# circuit.net
KiCad netlist of a schematic drawn in Altium Designer
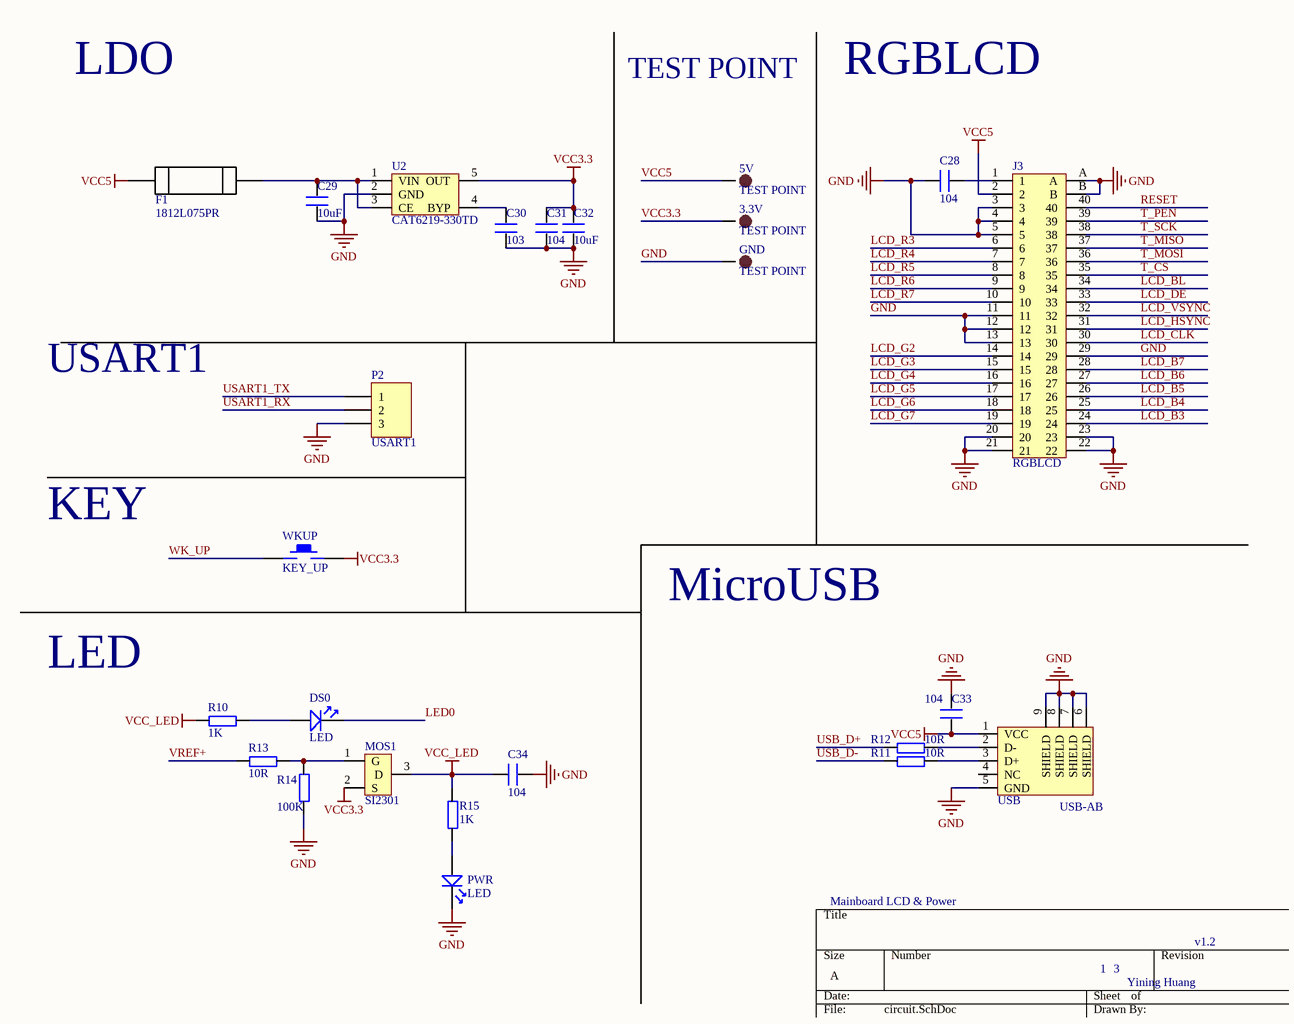
[diagram p0: circuit.SchDoc]

(export (version "E")
  (design (tool "Eeschema 10.0.6"))
  (components
    (comp (ref "3.3V")
      (value "TEST POINT")
      (footprint "TP-1.5")
      (description "测试点")
      (libsource (lib "STM32F767核心板封装库") (part "TEST-POINT"))
    )
    (comp (ref "5V")
      (value "TEST POINT")
      (footprint "TP-1.5")
      (description "测试点")
      (libsource (lib "STM32F767核心板封装库") (part "TEST-POINT"))
    )
    (comp (ref "C28") (value "104") (footprint "0805") (libsource (lib "STM32F767核心板封装库") (part "C")))
    (comp (ref "C29") (value "10uF") (footprint "0805") (libsource (lib "STM32F767核心板封装库") (part "C")))
    (comp (ref "C30") (value "103") (footprint "0805") (libsource (lib "STM32F767核心板封装库") (part "C")))
    (comp (ref "C31") (value "104") (footprint "0805") (libsource (lib "STM32F767核心板封装库") (part "C")))
    (comp (ref "C32") (value "10uF") (footprint "0805") (libsource (lib "STM32F767核心板封装库") (part "C")))
    (comp (ref "C33") (value "104") (footprint "0805") (libsource (lib "STM32F767核心板封装库") (part "C")))
    (comp (ref "C34") (value "104") (footprint "0805") (libsource (lib "STM32F767核心板封装库") (part "C")))
    (comp (ref "DS0")
      (value "LED")
      (footprint "SMDLED-0603")
      (libsource (lib "STM32F767核心板封装库") (part "LED"))
    )
    (comp (ref "F1")
      (value "1812L075PR")
      (footprint "*1812")
      (description "PTC Resettable Fuse 0.75A_hold_ 1.5A_trip_ 13.2VDC 100A 0.8W 0.2s 0.1Ohm SMD Solder Pad 1812 T/R")
      (fields (field (name "MF") "Littelfuse Inc."))
      (libsource (lib "1812L075PR") (part "1812L075PR"))
    )
    (comp (ref "GND")
      (value "TEST POINT")
      (footprint "TP-1.5")
      (description "测试点")
      (libsource (lib "STM32F767核心板封装库") (part "TEST-POINT"))
    )
    (comp (ref "J3")
      (value "RGBLCD")
      (footprint "FPC-TOP40")
      (description "FPC-40P-0.5mm")
      (libsource (lib "STM32F767核心板封装库") (part "FPC-40"))
    )
    (comp (ref "MOS1")
      (value "SI2301")
      (footprint "SO-G3/C2.5")
      (description "IRLML6401/SI2301")
      (libsource (lib "STM32F767核心板封装库") (part "MOS-P"))
    )
    (comp (ref "P2")
      (value "USART1")
      (footprint "HDR1X3")
      (description "Header, 3-Pin")
      (fields (field (name "PUBLISHER") "Altium Limited"))
      (libsource (lib "STM32F767核心板封装库") (part "Header 3"))
    )
    (comp (ref "PWR")
      (value "LED")
      (footprint "SMDLED-0603")
      (libsource (lib "STM32F767核心板封装库") (part "LED"))
    )
    (comp (ref "R10") (value "1K") (footprint "0805") (libsource (lib "STM32F767核心板封装库") (part "R")))
    (comp (ref "R11") (value "10R") (footprint "0805") (libsource (lib "STM32F767核心板封装库") (part "R")))
    (comp (ref "R12") (value "10R") (footprint "0805") (libsource (lib "STM32F767核心板封装库") (part "R")))
    (comp (ref "R13") (value "10R") (footprint "0805") (libsource (lib "STM32F767核心板封装库") (part "R")))
    (comp (ref "R14") (value "100K") (footprint "0805") (libsource (lib "STM32F767核心板封装库") (part "R")))
    (comp (ref "R15") (value "1K") (footprint "0805") (libsource (lib "STM32F767核心板封装库") (part "R")))
    (comp (ref "U2")
      (value "CAT6219-330TD")
      (footprint "SOT-23-5")
      (description "3.3V 500mA LDO")
      (libsource (lib "STM32F767核心板封装库") (part "CAT6219-330TD"))
    )
    (comp (ref "USB")
      (value "USB-AB")
      (footprint "USB_AB - 5S - B")
      (description "MicroUSB")
      (libsource (lib "STM32F767核心板封装库") (part "USB-AB"))
    )
    (comp (ref "WKUP")
      (value "KEY_UP")
      (footprint "KEY_SOP3625")
      (libsource (lib "STM32F767核心板封装库") (part "KEY_M"))
    )
  )
  (nets
    (net (code "1") (name "/LCD_B3") (class "Default")
      (node (ref "J3") (pin "24") (pinfunction "24_24") (pintype "passive"))
    )
    (net (code "2") (name "/LCD_B4") (class "Default")
      (node (ref "J3") (pin "25") (pinfunction "25_25") (pintype "passive"))
    )
    (net (code "3") (name "/LCD_B5") (class "Default")
      (node (ref "J3") (pin "26") (pinfunction "26_26") (pintype "passive"))
    )
    (net (code "4") (name "/LCD_B6") (class "Default")
      (node (ref "J3") (pin "27") (pinfunction "27_27") (pintype "passive"))
    )
    (net (code "5") (name "/LCD_B7") (class "Default")
      (node (ref "J3") (pin "28") (pinfunction "28_28") (pintype "passive"))
    )
    (net (code "6") (name "/LCD_BL") (class "Default")
      (node (ref "J3") (pin "34") (pinfunction "34_34") (pintype "passive"))
    )
    (net (code "7") (name "/LCD_CLK") (class "Default")
      (node (ref "J3") (pin "30") (pinfunction "30_30") (pintype "passive"))
    )
    (net (code "8") (name "/LCD_DE") (class "Default")
      (node (ref "J3") (pin "33") (pinfunction "33_33") (pintype "passive"))
    )
    (net (code "9") (name "/LCD_G2") (class "Default")
      (node (ref "J3") (pin "14") (pinfunction "14_14") (pintype "passive"))
    )
    (net (code "10") (name "/LCD_G3") (class "Default")
      (node (ref "J3") (pin "15") (pinfunction "15_15") (pintype "passive"))
    )
    (net (code "11") (name "/LCD_G4") (class "Default")
      (node (ref "J3") (pin "16") (pinfunction "16_16") (pintype "passive"))
    )
    (net (code "12") (name "/LCD_G5") (class "Default")
      (node (ref "J3") (pin "17") (pinfunction "17_17") (pintype "passive"))
    )
    (net (code "13") (name "/LCD_G6") (class "Default")
      (node (ref "J3") (pin "18") (pinfunction "18_18") (pintype "passive"))
    )
    (net (code "14") (name "/LCD_G7") (class "Default")
      (node (ref "J3") (pin "19") (pinfunction "19_19") (pintype "passive"))
    )
    (net (code "15") (name "/LCD_HSYNC") (class "Default")
      (node (ref "J3") (pin "31") (pinfunction "31_31") (pintype "passive"))
    )
    (net (code "16") (name "/LCD_R3") (class "Default")
      (node (ref "J3") (pin "6") (pinfunction "6_6") (pintype "passive"))
    )
    (net (code "17") (name "/LCD_R4") (class "Default")
      (node (ref "J3") (pin "7") (pinfunction "7_7") (pintype "passive"))
    )
    (net (code "18") (name "/LCD_R5") (class "Default")
      (node (ref "J3") (pin "8") (pinfunction "8_8") (pintype "passive"))
    )
    (net (code "19") (name "/LCD_R6") (class "Default")
      (node (ref "J3") (pin "9") (pinfunction "9_9") (pintype "passive"))
    )
    (net (code "20") (name "/LCD_R7") (class "Default")
      (node (ref "J3") (pin "10") (pinfunction "10_10") (pintype "passive"))
    )
    (net (code "21") (name "/LCD_VSYNC") (class "Default")
      (node (ref "J3") (pin "32") (pinfunction "32_32") (pintype "passive"))
    )
    (net (code "22") (name "/LED0") (class "Default")
      (node (ref "DS0") (pin "2") (pinfunction "2_2") (pintype "passive"))
    )
    (net (code "23") (name "/RESET") (class "Default")
      (node (ref "J3") (pin "40") (pinfunction "40_40") (pintype "passive"))
    )
    (net (code "24") (name "/T_CS") (class "Default")
      (node (ref "J3") (pin "35") (pinfunction "35_35") (pintype "passive"))
    )
    (net (code "25") (name "/T_MISO") (class "Default")
      (node (ref "J3") (pin "37") (pinfunction "37_37") (pintype "passive"))
    )
    (net (code "26") (name "/T_MOSI") (class "Default")
      (node (ref "J3") (pin "36") (pinfunction "36_36") (pintype "passive"))
    )
    (net (code "27") (name "/T_PEN") (class "Default")
      (node (ref "J3") (pin "39") (pinfunction "39_39") (pintype "passive"))
    )
    (net (code "28") (name "/T_SCK") (class "Default")
      (node (ref "J3") (pin "38") (pinfunction "38_38") (pintype "passive"))
    )
    (net (code "29") (name "/USART1_RX") (class "Default")
      (node (ref "P2") (pin "2") (pinfunction "2_2") (pintype "passive"))
    )
    (net (code "30") (name "/USART1_TX") (class "Default")
      (node (ref "P2") (pin "1") (pinfunction "1_1") (pintype "passive"))
    )
    (net (code "31") (name "/USB_D+") (class "Default") (node (ref "R12") (pin "1") (pintype "passive")))
    (net (code "32") (name "/USB_D-") (class "Default") (node (ref "R11") (pin "1") (pintype "passive")))
    (net (code "33") (name "/VREF+") (class "Default") (node (ref "R13") (pin "1") (pintype "passive")))
    (net (code "34") (name "/WK_UP") (class "Default")
      (node (ref "WKUP") (pin "1") (pinfunction "1_1") (pintype "passive"))
    )
    (net (code "35") (name "GND") (class "Default")
      (node (ref "C28") (pin "1") (pintype "passive"))
      (node (ref "C29") (pin "1") (pintype "passive"))
      (node (ref "C30") (pin "1") (pintype "passive"))
      (node (ref "C31") (pin "1") (pintype "passive"))
      (node (ref "C32") (pin "1") (pintype "passive"))
      (node (ref "C33") (pin "2") (pintype "passive"))
      (node (ref "C34") (pin "2") (pintype "passive"))
      (node (ref "GND") (pin "1") (pinfunction "1_1") (pintype "passive"))
      (node (ref "J3") (pin "11") (pinfunction "11_11") (pintype "passive"))
      (node (ref "J3") (pin "12") (pinfunction "12_12") (pintype "passive"))
      (node (ref "J3") (pin "13") (pinfunction "13_13") (pintype "passive"))
      (node (ref "J3") (pin "20") (pinfunction "20_20") (pintype "passive"))
      (node (ref "J3") (pin "21") (pinfunction "21_21") (pintype "passive"))
      (node (ref "J3") (pin "22") (pinfunction "22_22") (pintype "passive"))
      (node (ref "J3") (pin "23") (pinfunction "23_23") (pintype "passive"))
      (node (ref "J3") (pin "29") (pinfunction "29_29") (pintype "passive"))
      (node (ref "J3") (pin "3") (pinfunction "3_3") (pintype "passive"))
      (node (ref "J3") (pin "4") (pinfunction "4_4") (pintype "passive"))
      (node (ref "J3") (pin "5") (pinfunction "5_5") (pintype "passive"))
      (node (ref "J3") (pin "A") (pinfunction "A_A") (pintype "passive"))
      (node (ref "J3") (pin "B") (pinfunction "B_B") (pintype "passive"))
      (node (ref "P2") (pin "3") (pinfunction "3_3") (pintype "passive"))
      (node (ref "PWR") (pin "2") (pinfunction "2_2") (pintype "passive"))
      (node (ref "R14") (pin "1") (pintype "passive"))
      (node (ref "U2") (pin "2") (pinfunction "GND_2") (pintype "passive"))
      (node (ref "USB") (pin "5") (pinfunction "GND_5") (pintype "passive"))
      (node (ref "USB") (pin "6") (pinfunction "SHIELD_6") (pintype "passive"))
      (node (ref "USB") (pin "7") (pinfunction "SHIELD_7") (pintype "passive"))
      (node (ref "USB") (pin "8") (pinfunction "SHIELD_8") (pintype "passive"))
      (node (ref "USB") (pin "9") (pinfunction "SHIELD_9") (pintype "passive"))
    )
    (net (code "36") (name "Net-(C28-Pad2)") (class "Default")
      (node (ref "C28") (pin "2") (pintype "passive"))
      (node (ref "J3") (pin "1") (pinfunction "1_1") (pintype "passive"))
    )
    (net (code "37") (name "Net-(DS0-Pad1)") (class "Default")
      (node (ref "DS0") (pin "1") (pinfunction "1_1") (pintype "passive"))
      (node (ref "R10") (pin "2") (pintype "passive"))
    )
    (net (code "38") (name "Net-(MOS1-G)") (class "Default")
      (node (ref "MOS1") (pin "1") (pinfunction "G_1") (pintype "passive"))
      (node (ref "R13") (pin "2") (pintype "passive"))
      (node (ref "R14") (pin "2") (pintype "passive"))
    )
    (net (code "39") (name "Net-(PWR-Pad1)") (class "Default")
      (node (ref "PWR") (pin "1") (pinfunction "1_1") (pintype "passive"))
      (node (ref "R15") (pin "1") (pintype "passive"))
    )
    (net (code "40") (name "Net-(U2-BYP)") (class "Default")
      (node (ref "C30") (pin "2") (pintype "passive"))
      (node (ref "U2") (pin "4") (pinfunction "BYP_4") (pintype "passive"))
    )
    (net (code "41") (name "Net-(U2-CE)") (class "Default")
      (node (ref "C29") (pin "2") (pintype "passive"))
      (node (ref "F1") (pin "2") (pinfunction "2_2") (pintype "passive"))
      (node (ref "U2") (pin "1") (pinfunction "VIN_1") (pintype "passive"))
      (node (ref "U2") (pin "3") (pinfunction "CE_3") (pintype "passive"))
    )
    (net (code "42") (name "Net-(USB-D+)") (class "Default")
      (node (ref "R11") (pin "2") (pintype "passive"))
      (node (ref "USB") (pin "3") (pinfunction "D+_3") (pintype "passive"))
    )
    (net (code "43") (name "Net-(USB-D-)") (class "Default")
      (node (ref "R12") (pin "2") (pintype "passive"))
      (node (ref "USB") (pin "2") (pinfunction "D-_2") (pintype "passive"))
    )
    (net (code "44") (name "VCC3.3") (class "Default")
      (node (ref "3.3V") (pin "1") (pinfunction "1_1") (pintype "passive"))
      (node (ref "C31") (pin "2") (pintype "passive"))
      (node (ref "C32") (pin "2") (pintype "passive"))
      (node (ref "MOS1") (pin "2") (pinfunction "S_2") (pintype "passive"))
      (node (ref "U2") (pin "5") (pinfunction "OUT_5") (pintype "passive"))
      (node (ref "WKUP") (pin "2") (pinfunction "2_2") (pintype "passive"))
    )
    (net (code "45") (name "VCC5") (class "Default")
      (node (ref "5V") (pin "1") (pinfunction "1_1") (pintype "passive"))
      (node (ref "C33") (pin "1") (pintype "passive"))
      (node (ref "F1") (pin "1") (pinfunction "1_1") (pintype "passive"))
      (node (ref "J3") (pin "2") (pinfunction "2_2") (pintype "passive"))
      (node (ref "USB") (pin "1") (pinfunction "VCC_1") (pintype "passive"))
    )
    (net (code "46") (name "VCC_LED") (class "Default")
      (node (ref "C34") (pin "1") (pintype "passive"))
      (node (ref "MOS1") (pin "3") (pinfunction "D_3") (pintype "passive"))
      (node (ref "R10") (pin "1") (pintype "passive"))
      (node (ref "R15") (pin "2") (pintype "passive"))
    )
    (net (code "47") (name "unconnected-(USB-NC-Pad4)") (class "Default")
      (node (ref "USB") (pin "4") (pinfunction "NC_4") (pintype "passive"))
    )
  )
)
